# passive_balancing.net
KiCad netlist of a schematic drawn in Altium Designer
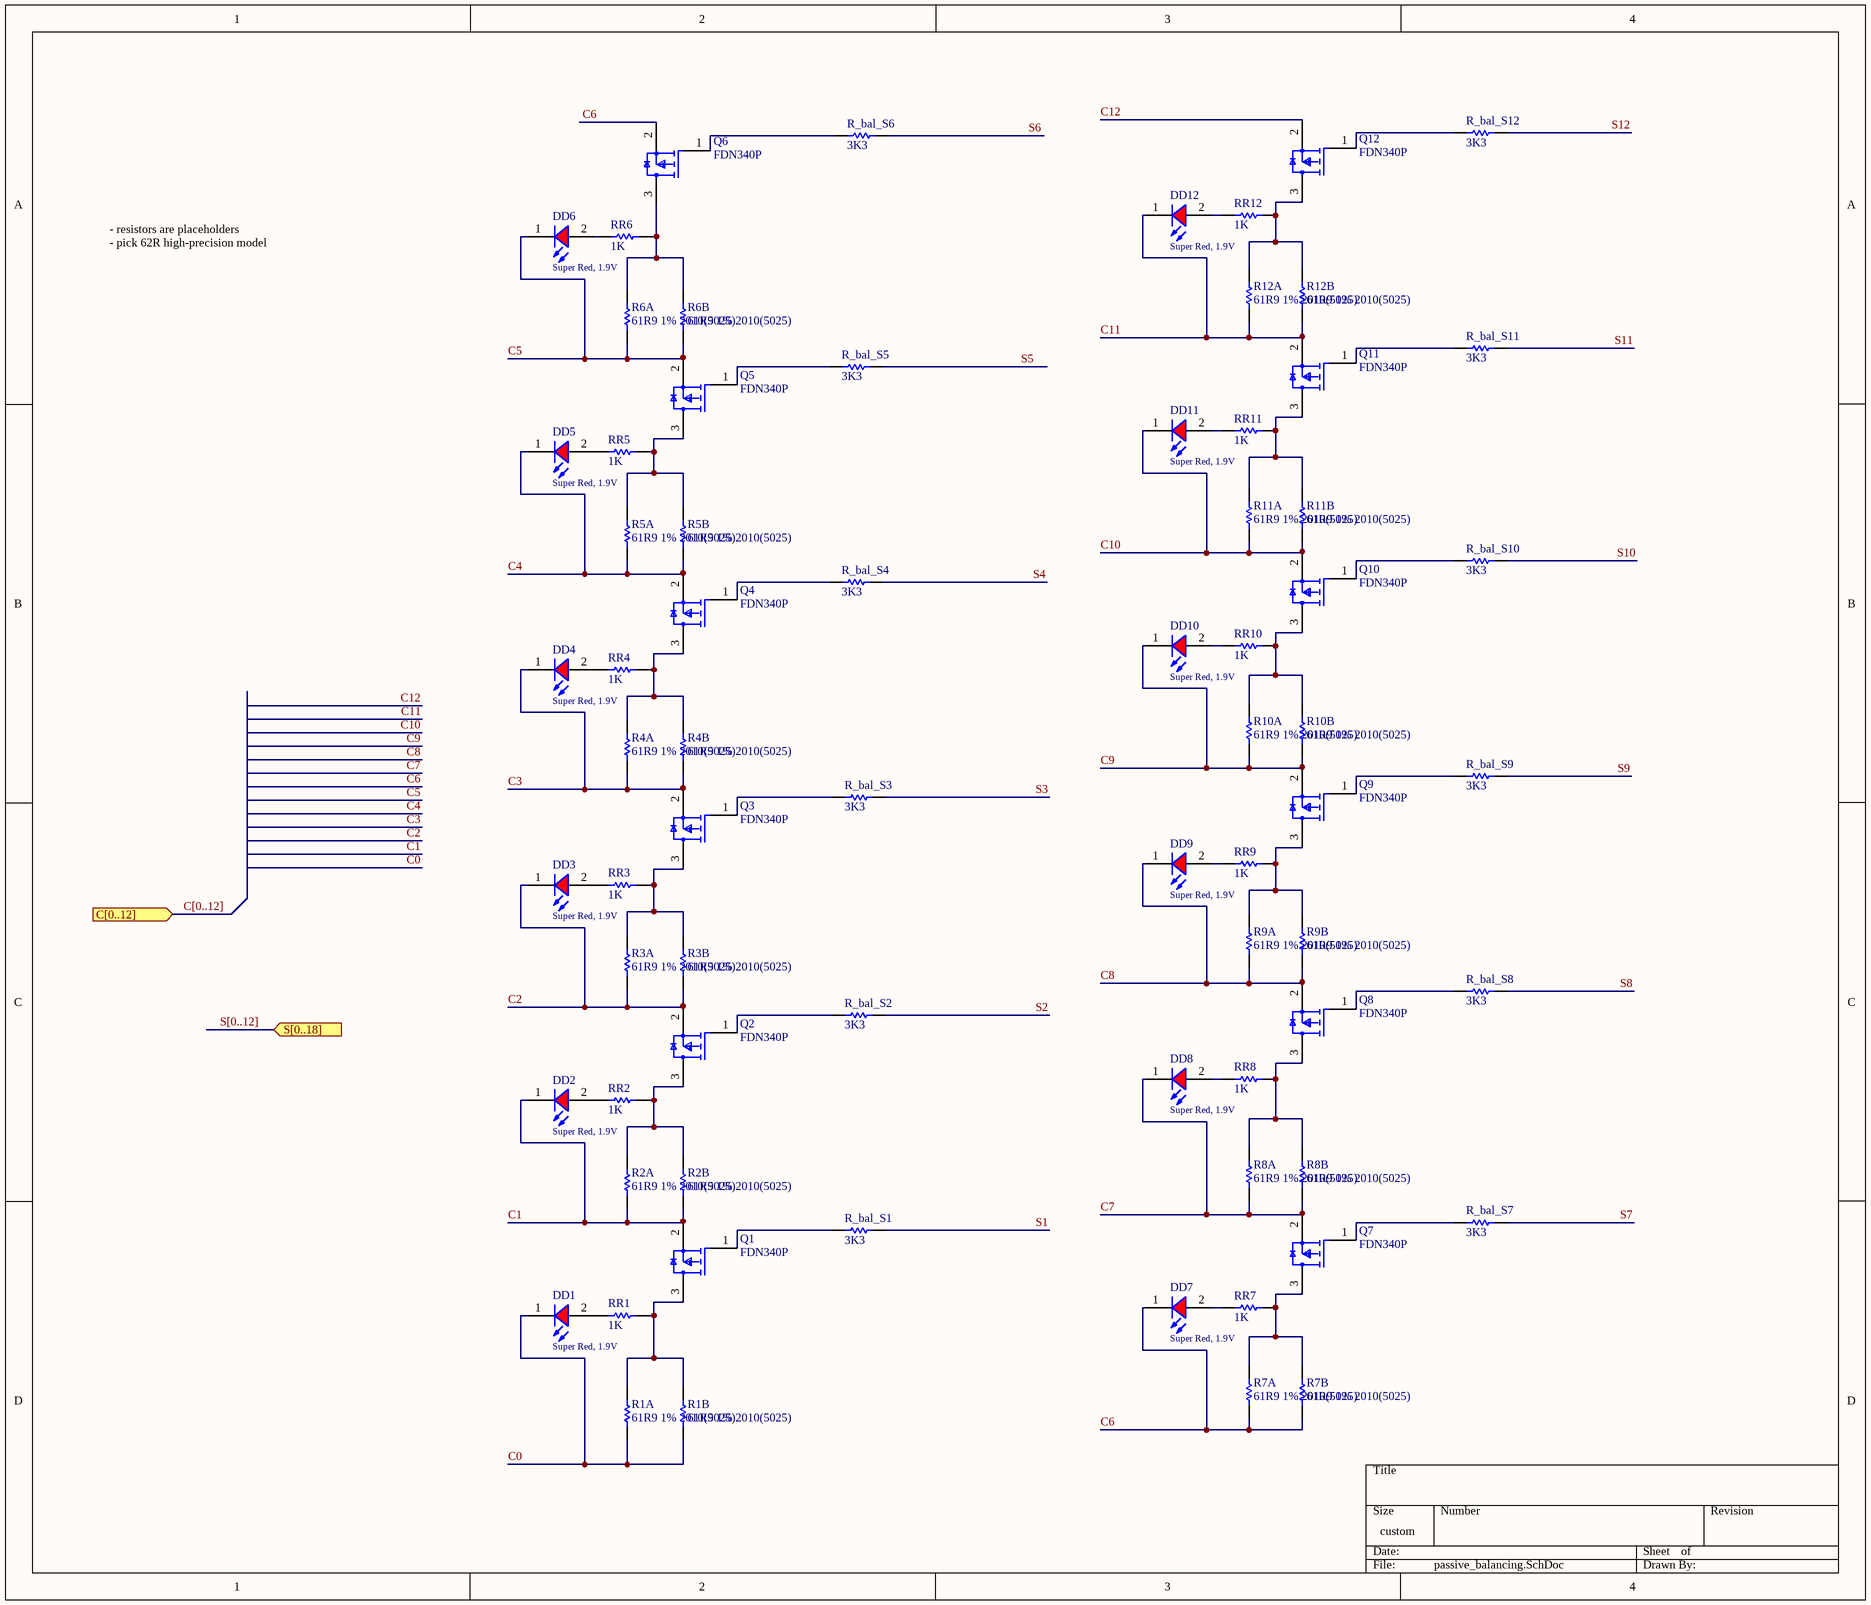
[diagram p0: passive_balancing.SchDoc]

(export (version "E")
  (design (tool "Eeschema 10.0.6"))
  (components
    (comp (ref "DD1")
      (value "Super Red, 1.9V")
      (footprint "WL-SMCW_0603_H=0.7mm")
      (description "WL-SMCW SMT Mono-color Chip LED Waterclear, size 0603, Super Red, 1.9V, 140deg")
      (fields (field (name "PART NUMBER") "150060SS75000") (field (name "PUBLISHER") "Wurth Elektronik"))
      (libsource (lib "LEDs") (part "150060SS75000"))
    )
    (comp (ref "DD2")
      (value "Super Red, 1.9V")
      (footprint "WL-SMCW_0603_H=0.7mm")
      (description "WL-SMCW SMT Mono-color Chip LED Waterclear, size 0603, Super Red, 1.9V, 140deg")
      (fields (field (name "PART NUMBER") "150060SS75000") (field (name "PUBLISHER") "Wurth Elektronik"))
      (libsource (lib "LEDs") (part "150060SS75000"))
    )
    (comp (ref "DD3")
      (value "Super Red, 1.9V")
      (footprint "WL-SMCW_0603_H=0.7mm")
      (description "WL-SMCW SMT Mono-color Chip LED Waterclear, size 0603, Super Red, 1.9V, 140deg")
      (fields (field (name "PART NUMBER") "150060SS75000") (field (name "PUBLISHER") "Wurth Elektronik"))
      (libsource (lib "LEDs") (part "150060SS75000"))
    )
    (comp (ref "DD4")
      (value "Super Red, 1.9V")
      (footprint "WL-SMCW_0603_H=0.7mm")
      (description "WL-SMCW SMT Mono-color Chip LED Waterclear, size 0603, Super Red, 1.9V, 140deg")
      (fields (field (name "PART NUMBER") "150060SS75000") (field (name "PUBLISHER") "Wurth Elektronik"))
      (libsource (lib "LEDs") (part "150060SS75000"))
    )
    (comp (ref "DD5")
      (value "Super Red, 1.9V")
      (footprint "WL-SMCW_0603_H=0.7mm")
      (description "WL-SMCW SMT Mono-color Chip LED Waterclear, size 0603, Super Red, 1.9V, 140deg")
      (fields (field (name "PART NUMBER") "150060SS75000") (field (name "PUBLISHER") "Wurth Elektronik"))
      (libsource (lib "LEDs") (part "150060SS75000"))
    )
    (comp (ref "DD6")
      (value "Super Red, 1.9V")
      (footprint "WL-SMCW_0603_H=0.7mm")
      (description "WL-SMCW SMT Mono-color Chip LED Waterclear, size 0603, Super Red, 1.9V, 140deg")
      (fields (field (name "PART NUMBER") "150060SS75000") (field (name "PUBLISHER") "Wurth Elektronik"))
      (libsource (lib "LEDs") (part "150060SS75000"))
    )
    (comp (ref "DD7")
      (value "Super Red, 1.9V")
      (footprint "WL-SMCW_0603_H=0.7mm")
      (description "WL-SMCW SMT Mono-color Chip LED Waterclear, size 0603, Super Red, 1.9V, 140deg")
      (fields (field (name "PART NUMBER") "150060SS75000") (field (name "PUBLISHER") "Wurth Elektronik"))
      (libsource (lib "LEDs") (part "150060SS75000"))
    )
    (comp (ref "DD8")
      (value "Super Red, 1.9V")
      (footprint "WL-SMCW_0603_H=0.7mm")
      (description "WL-SMCW SMT Mono-color Chip LED Waterclear, size 0603, Super Red, 1.9V, 140deg")
      (fields (field (name "PART NUMBER") "150060SS75000") (field (name "PUBLISHER") "Wurth Elektronik"))
      (libsource (lib "LEDs") (part "150060SS75000"))
    )
    (comp (ref "DD9")
      (value "Super Red, 1.9V")
      (footprint "WL-SMCW_0603_H=0.7mm")
      (description "WL-SMCW SMT Mono-color Chip LED Waterclear, size 0603, Super Red, 1.9V, 140deg")
      (fields (field (name "PART NUMBER") "150060SS75000") (field (name "PUBLISHER") "Wurth Elektronik"))
      (libsource (lib "LEDs") (part "150060SS75000"))
    )
    (comp (ref "DD10")
      (value "Super Red, 1.9V")
      (footprint "WL-SMCW_0603_H=0.7mm")
      (description "WL-SMCW SMT Mono-color Chip LED Waterclear, size 0603, Super Red, 1.9V, 140deg")
      (fields (field (name "PART NUMBER") "150060SS75000") (field (name "PUBLISHER") "Wurth Elektronik"))
      (libsource (lib "LEDs") (part "150060SS75000"))
    )
    (comp (ref "DD11")
      (value "Super Red, 1.9V")
      (footprint "WL-SMCW_0603_H=0.7mm")
      (description "WL-SMCW SMT Mono-color Chip LED Waterclear, size 0603, Super Red, 1.9V, 140deg")
      (fields (field (name "PART NUMBER") "150060SS75000") (field (name "PUBLISHER") "Wurth Elektronik"))
      (libsource (lib "LEDs") (part "150060SS75000"))
    )
    (comp (ref "DD12")
      (value "Super Red, 1.9V")
      (footprint "WL-SMCW_0603_H=0.7mm")
      (description "WL-SMCW SMT Mono-color Chip LED Waterclear, size 0603, Super Red, 1.9V, 140deg")
      (fields (field (name "PART NUMBER") "150060SS75000") (field (name "PUBLISHER") "Wurth Elektronik"))
      (libsource (lib "LEDs") (part "150060SS75000"))
    )
    (comp (ref "Q1")
      (value "FDN340P")
      (footprint "FP-527AG-MFG")
      (description "MOSFET P-CH 20V 2A SSOT3")
      (libsource (lib "Altium Content Vault") (part "d23f43cc42f60b967b7caccf14518fd"))
    )
    (comp (ref "Q2")
      (value "FDN340P")
      (footprint "FP-527AG-MFG")
      (description "MOSFET P-CH 20V 2A SSOT3")
      (libsource (lib "Altium Content Vault") (part "d23f43cc42f60b967b7caccf14518fd"))
    )
    (comp (ref "Q3")
      (value "FDN340P")
      (footprint "FP-527AG-MFG")
      (description "MOSFET P-CH 20V 2A SSOT3")
      (libsource (lib "Altium Content Vault") (part "d23f43cc42f60b967b7caccf14518fd"))
    )
    (comp (ref "Q4")
      (value "FDN340P")
      (footprint "FP-527AG-MFG")
      (description "MOSFET P-CH 20V 2A SSOT3")
      (libsource (lib "Altium Content Vault") (part "d23f43cc42f60b967b7caccf14518fd"))
    )
    (comp (ref "Q5")
      (value "FDN340P")
      (footprint "FP-527AG-MFG")
      (description "MOSFET P-CH 20V 2A SSOT3")
      (libsource (lib "Altium Content Vault") (part "d23f43cc42f60b967b7caccf14518fd"))
    )
    (comp (ref "Q6")
      (value "FDN340P")
      (footprint "FP-527AG-MFG")
      (description "MOSFET P-CH 20V 2A SSOT3")
      (libsource (lib "Altium Content Vault") (part "d23f43cc42f60b967b7caccf14518fd"))
    )
    (comp (ref "Q7")
      (value "FDN340P")
      (footprint "FP-527AG-MFG")
      (description "MOSFET P-CH 20V 2A SSOT3")
      (libsource (lib "Altium Content Vault") (part "d23f43cc42f60b967b7caccf14518fd"))
    )
    (comp (ref "Q8")
      (value "FDN340P")
      (footprint "FP-527AG-MFG")
      (description "MOSFET P-CH 20V 2A SSOT3")
      (libsource (lib "Altium Content Vault") (part "d23f43cc42f60b967b7caccf14518fd"))
    )
    (comp (ref "Q9")
      (value "FDN340P")
      (footprint "FP-527AG-MFG")
      (description "MOSFET P-CH 20V 2A SSOT3")
      (libsource (lib "Altium Content Vault") (part "d23f43cc42f60b967b7caccf14518fd"))
    )
    (comp (ref "Q10")
      (value "FDN340P")
      (footprint "FP-527AG-MFG")
      (description "MOSFET P-CH 20V 2A SSOT3")
      (libsource (lib "Altium Content Vault") (part "d23f43cc42f60b967b7caccf14518fd"))
    )
    (comp (ref "Q11")
      (value "FDN340P")
      (footprint "FP-527AG-MFG")
      (description "MOSFET P-CH 20V 2A SSOT3")
      (libsource (lib "Altium Content Vault") (part "d23f43cc42f60b967b7caccf14518fd"))
    )
    (comp (ref "Q12")
      (value "FDN340P")
      (footprint "FP-527AG-MFG")
      (description "MOSFET P-CH 20V 2A SSOT3")
      (libsource (lib "Altium Content Vault") (part "d23f43cc42f60b967b7caccf14518fd"))
    )
    (comp (ref "R1A")
      (value "61R9 1% 2010(5025)")
      (footprint "RESC2010(5025)_M")
      (description "61R9 0.75W 1% 2010 (5025 Metric)  SMD")
      (fields (field (name "POWER") "0.75 W") (field (name "TOLERANCE") "1 %"))
      (libsource (lib "Altium Content Vault") (part "RES"))
    )
    (comp (ref "R1B")
      (value "61R9 1% 2010(5025)")
      (footprint "RESC2010(5025)_M")
      (description "61R9 0.75W 1% 2010 (5025 Metric)  SMD")
      (fields (field (name "POWER") "0.75 W") (field (name "TOLERANCE") "1 %"))
      (libsource (lib "Altium Content Vault") (part "RES"))
    )
    (comp (ref "R2A")
      (value "61R9 1% 2010(5025)")
      (footprint "RESC2010(5025)_M")
      (description "61R9 0.75W 1% 2010 (5025 Metric)  SMD")
      (fields (field (name "POWER") "0.75 W") (field (name "TOLERANCE") "1 %"))
      (libsource (lib "Altium Content Vault") (part "RES"))
    )
    (comp (ref "R2B")
      (value "61R9 1% 2010(5025)")
      (footprint "RESC2010(5025)_M")
      (description "61R9 0.75W 1% 2010 (5025 Metric)  SMD")
      (fields (field (name "POWER") "0.75 W") (field (name "TOLERANCE") "1 %"))
      (libsource (lib "Altium Content Vault") (part "RES"))
    )
    (comp (ref "R3A")
      (value "61R9 1% 2010(5025)")
      (footprint "RESC2010(5025)_M")
      (description "61R9 0.75W 1% 2010 (5025 Metric)  SMD")
      (fields (field (name "POWER") "0.75 W") (field (name "TOLERANCE") "1 %"))
      (libsource (lib "Altium Content Vault") (part "RES"))
    )
    (comp (ref "R3B")
      (value "61R9 1% 2010(5025)")
      (footprint "RESC2010(5025)_M")
      (description "61R9 0.75W 1% 2010 (5025 Metric)  SMD")
      (fields (field (name "POWER") "0.75 W") (field (name "TOLERANCE") "1 %"))
      (libsource (lib "Altium Content Vault") (part "RES"))
    )
    (comp (ref "R4A")
      (value "61R9 1% 2010(5025)")
      (footprint "RESC2010(5025)_M")
      (description "61R9 0.75W 1% 2010 (5025 Metric)  SMD")
      (fields (field (name "POWER") "0.75 W") (field (name "TOLERANCE") "1 %"))
      (libsource (lib "Altium Content Vault") (part "RES"))
    )
    (comp (ref "R4B")
      (value "61R9 1% 2010(5025)")
      (footprint "RESC2010(5025)_M")
      (description "61R9 0.75W 1% 2010 (5025 Metric)  SMD")
      (fields (field (name "POWER") "0.75 W") (field (name "TOLERANCE") "1 %"))
      (libsource (lib "Altium Content Vault") (part "RES"))
    )
    (comp (ref "R5A")
      (value "61R9 1% 2010(5025)")
      (footprint "RESC2010(5025)_M")
      (description "61R9 0.75W 1% 2010 (5025 Metric)  SMD")
      (fields (field (name "POWER") "0.75 W") (field (name "TOLERANCE") "1 %"))
      (libsource (lib "Altium Content Vault") (part "RES"))
    )
    (comp (ref "R5B")
      (value "61R9 1% 2010(5025)")
      (footprint "RESC2010(5025)_M")
      (description "61R9 0.75W 1% 2010 (5025 Metric)  SMD")
      (fields (field (name "POWER") "0.75 W") (field (name "TOLERANCE") "1 %"))
      (libsource (lib "Altium Content Vault") (part "RES"))
    )
    (comp (ref "R6A")
      (value "61R9 1% 2010(5025)")
      (footprint "RESC2010(5025)_M")
      (description "61R9 0.75W 1% 2010 (5025 Metric)  SMD")
      (fields (field (name "POWER") "0.75 W") (field (name "TOLERANCE") "1 %"))
      (libsource (lib "Altium Content Vault") (part "RES"))
    )
    (comp (ref "R6B")
      (value "61R9 1% 2010(5025)")
      (footprint "RESC2010(5025)_M")
      (description "61R9 0.75W 1% 2010 (5025 Metric)  SMD")
      (fields (field (name "POWER") "0.75 W") (field (name "TOLERANCE") "1 %"))
      (libsource (lib "Altium Content Vault") (part "RES"))
    )
    (comp (ref "R7A")
      (value "61R9 1% 2010(5025)")
      (footprint "RESC2010(5025)_M")
      (description "61R9 0.75W 1% 2010 (5025 Metric)  SMD")
      (fields (field (name "POWER") "0.75 W") (field (name "TOLERANCE") "1 %"))
      (libsource (lib "Altium Content Vault") (part "RES"))
    )
    (comp (ref "R7B")
      (value "61R9 1% 2010(5025)")
      (footprint "RESC2010(5025)_M")
      (description "61R9 0.75W 1% 2010 (5025 Metric)  SMD")
      (fields (field (name "POWER") "0.75 W") (field (name "TOLERANCE") "1 %"))
      (libsource (lib "Altium Content Vault") (part "RES"))
    )
    (comp (ref "R8A")
      (value "61R9 1% 2010(5025)")
      (footprint "RESC2010(5025)_M")
      (description "61R9 0.75W 1% 2010 (5025 Metric)  SMD")
      (fields (field (name "POWER") "0.75 W") (field (name "TOLERANCE") "1 %"))
      (libsource (lib "Altium Content Vault") (part "RES"))
    )
    (comp (ref "R8B")
      (value "61R9 1% 2010(5025)")
      (footprint "RESC2010(5025)_M")
      (description "61R9 0.75W 1% 2010 (5025 Metric)  SMD")
      (fields (field (name "POWER") "0.75 W") (field (name "TOLERANCE") "1 %"))
      (libsource (lib "Altium Content Vault") (part "RES"))
    )
    (comp (ref "R9A")
      (value "61R9 1% 2010(5025)")
      (footprint "RESC2010(5025)_M")
      (description "61R9 0.75W 1% 2010 (5025 Metric)  SMD")
      (fields (field (name "POWER") "0.75 W") (field (name "TOLERANCE") "1 %"))
      (libsource (lib "Altium Content Vault") (part "RES"))
    )
    (comp (ref "R9B")
      (value "61R9 1% 2010(5025)")
      (footprint "RESC2010(5025)_M")
      (description "61R9 0.75W 1% 2010 (5025 Metric)  SMD")
      (fields (field (name "POWER") "0.75 W") (field (name "TOLERANCE") "1 %"))
      (libsource (lib "Altium Content Vault") (part "RES"))
    )
    (comp (ref "R10A")
      (value "61R9 1% 2010(5025)")
      (footprint "RESC2010(5025)_M")
      (description "61R9 0.75W 1% 2010 (5025 Metric)  SMD")
      (fields (field (name "POWER") "0.75 W") (field (name "TOLERANCE") "1 %"))
      (libsource (lib "Altium Content Vault") (part "RES"))
    )
    (comp (ref "R10B")
      (value "61R9 1% 2010(5025)")
      (footprint "RESC2010(5025)_M")
      (description "61R9 0.75W 1% 2010 (5025 Metric)  SMD")
      (fields (field (name "POWER") "0.75 W") (field (name "TOLERANCE") "1 %"))
      (libsource (lib "Altium Content Vault") (part "RES"))
    )
    (comp (ref "R11A")
      (value "61R9 1% 2010(5025)")
      (footprint "RESC2010(5025)_M")
      (description "61R9 0.75W 1% 2010 (5025 Metric)  SMD")
      (fields (field (name "POWER") "0.75 W") (field (name "TOLERANCE") "1 %"))
      (libsource (lib "Altium Content Vault") (part "RES"))
    )
    (comp (ref "R11B")
      (value "61R9 1% 2010(5025)")
      (footprint "RESC2010(5025)_M")
      (description "61R9 0.75W 1% 2010 (5025 Metric)  SMD")
      (fields (field (name "POWER") "0.75 W") (field (name "TOLERANCE") "1 %"))
      (libsource (lib "Altium Content Vault") (part "RES"))
    )
    (comp (ref "R12A")
      (value "61R9 1% 2010(5025)")
      (footprint "RESC2010(5025)_M")
      (description "61R9 0.75W 1% 2010 (5025 Metric)  SMD")
      (fields (field (name "POWER") "0.75 W") (field (name "TOLERANCE") "1 %"))
      (libsource (lib "Altium Content Vault") (part "RES"))
    )
    (comp (ref "R12B")
      (value "61R9 1% 2010(5025)")
      (footprint "RESC2010(5025)_M")
      (description "61R9 0.75W 1% 2010 (5025 Metric)  SMD")
      (fields (field (name "POWER") "0.75 W") (field (name "TOLERANCE") "1 %"))
      (libsource (lib "Altium Content Vault") (part "RES"))
    )
    (comp (ref "RR1")
      (value "1K")
      (footprint "RESC0603(1608)_N")
      (description "Chipwiderstand, SMD, Baureihe MC, 1%")
      (fields (field (name "MANUFACTURER") "Multicomp") (field (name "POWER") "100mW"))
      (libsource (lib "Res&Caps") (part "Res 1K"))
    )
    (comp (ref "RR2")
      (value "1K")
      (footprint "RESC0603(1608)_N")
      (description "Chipwiderstand, SMD, Baureihe MC, 1%")
      (fields (field (name "MANUFACTURER") "Multicomp") (field (name "POWER") "100mW"))
      (libsource (lib "Res&Caps") (part "Res 1K"))
    )
    (comp (ref "RR3")
      (value "1K")
      (footprint "RESC0603(1608)_N")
      (description "Chipwiderstand, SMD, Baureihe MC, 1%")
      (fields (field (name "MANUFACTURER") "Multicomp") (field (name "POWER") "100mW"))
      (libsource (lib "Res&Caps") (part "Res 1K"))
    )
    (comp (ref "RR4")
      (value "1K")
      (footprint "RESC0603(1608)_N")
      (description "Chipwiderstand, SMD, Baureihe MC, 1%")
      (fields (field (name "MANUFACTURER") "Multicomp") (field (name "POWER") "100mW"))
      (libsource (lib "Res&Caps") (part "Res 1K"))
    )
    (comp (ref "RR5")
      (value "1K")
      (footprint "RESC0603(1608)_N")
      (description "Chipwiderstand, SMD, Baureihe MC, 1%")
      (fields (field (name "MANUFACTURER") "Multicomp") (field (name "POWER") "100mW"))
      (libsource (lib "Res&Caps") (part "Res 1K"))
    )
    (comp (ref "RR6")
      (value "1K")
      (footprint "RESC0603(1608)_N")
      (description "Chipwiderstand, SMD, Baureihe MC, 1%")
      (fields (field (name "MANUFACTURER") "Multicomp") (field (name "POWER") "100mW"))
      (libsource (lib "Res&Caps") (part "Res 1K"))
    )
    (comp (ref "RR7")
      (value "1K")
      (footprint "RESC0603(1608)_N")
      (description "Chipwiderstand, SMD, Baureihe MC, 1%")
      (fields (field (name "MANUFACTURER") "Multicomp") (field (name "POWER") "100mW"))
      (libsource (lib "Res&Caps") (part "Res 1K"))
    )
    (comp (ref "RR8")
      (value "1K")
      (footprint "RESC0603(1608)_N")
      (description "Chipwiderstand, SMD, Baureihe MC, 1%")
      (fields (field (name "MANUFACTURER") "Multicomp") (field (name "POWER") "100mW"))
      (libsource (lib "Res&Caps") (part "Res 1K"))
    )
    (comp (ref "RR9")
      (value "1K")
      (footprint "RESC0603(1608)_N")
      (description "Chipwiderstand, SMD, Baureihe MC, 1%")
      (fields (field (name "MANUFACTURER") "Multicomp") (field (name "POWER") "100mW"))
      (libsource (lib "Res&Caps") (part "Res 1K"))
    )
    (comp (ref "RR10")
      (value "1K")
      (footprint "RESC0603(1608)_N")
      (description "Chipwiderstand, SMD, Baureihe MC, 1%")
      (fields (field (name "MANUFACTURER") "Multicomp") (field (name "POWER") "100mW"))
      (libsource (lib "Res&Caps") (part "Res 1K"))
    )
    (comp (ref "RR11")
      (value "1K")
      (footprint "RESC0603(1608)_N")
      (description "Chipwiderstand, SMD, Baureihe MC, 1%")
      (fields (field (name "MANUFACTURER") "Multicomp") (field (name "POWER") "100mW"))
      (libsource (lib "Res&Caps") (part "Res 1K"))
    )
    (comp (ref "RR12")
      (value "1K")
      (footprint "RESC0603(1608)_N")
      (description "Chipwiderstand, SMD, Baureihe MC, 1%")
      (fields (field (name "MANUFACTURER") "Multicomp") (field (name "POWER") "100mW"))
      (libsource (lib "Res&Caps") (part "Res 1K"))
    )
    (comp (ref "R_bal_S1")
      (value "3K3")
      (footprint "RESC0603(1608)_N")
      (description "Chipwiderstand, SMD, Baureihe MC, 1%")
      (fields (field (name "MANUFACTURER") "Multicomp") (field (name "POWER") "100mW"))
      (libsource (lib "Res&Caps") (part "Res 3K3"))
    )
    (comp (ref "R_bal_S2")
      (value "3K3")
      (footprint "RESC0603(1608)_N")
      (description "Chipwiderstand, SMD, Baureihe MC, 1%")
      (fields (field (name "MANUFACTURER") "Multicomp") (field (name "POWER") "100mW"))
      (libsource (lib "Res&Caps") (part "Res 3K3"))
    )
    (comp (ref "R_bal_S3")
      (value "3K3")
      (footprint "RESC0603(1608)_N")
      (description "Chipwiderstand, SMD, Baureihe MC, 1%")
      (fields (field (name "MANUFACTURER") "Multicomp") (field (name "POWER") "100mW"))
      (libsource (lib "Res&Caps") (part "Res 3K3"))
    )
    (comp (ref "R_bal_S4")
      (value "3K3")
      (footprint "RESC0603(1608)_N")
      (description "Chipwiderstand, SMD, Baureihe MC, 1%")
      (fields (field (name "MANUFACTURER") "Multicomp") (field (name "POWER") "100mW"))
      (libsource (lib "Res&Caps") (part "Res 3K3"))
    )
    (comp (ref "R_bal_S5")
      (value "3K3")
      (footprint "RESC0603(1608)_N")
      (description "Chipwiderstand, SMD, Baureihe MC, 1%")
      (fields (field (name "MANUFACTURER") "Multicomp") (field (name "POWER") "100mW"))
      (libsource (lib "Res&Caps") (part "Res 3K3"))
    )
    (comp (ref "R_bal_S6")
      (value "3K3")
      (footprint "RESC0603(1608)_N")
      (description "Chipwiderstand, SMD, Baureihe MC, 1%")
      (fields (field (name "MANUFACTURER") "Multicomp") (field (name "POWER") "100mW"))
      (libsource (lib "Res&Caps") (part "Res 3K3"))
    )
    (comp (ref "R_bal_S7")
      (value "3K3")
      (footprint "RESC0603(1608)_N")
      (description "Chipwiderstand, SMD, Baureihe MC, 1%")
      (fields (field (name "MANUFACTURER") "Multicomp") (field (name "POWER") "100mW"))
      (libsource (lib "Res&Caps") (part "Res 3K3"))
    )
    (comp (ref "R_bal_S8")
      (value "3K3")
      (footprint "RESC0603(1608)_N")
      (description "Chipwiderstand, SMD, Baureihe MC, 1%")
      (fields (field (name "MANUFACTURER") "Multicomp") (field (name "POWER") "100mW"))
      (libsource (lib "Res&Caps") (part "Res 3K3"))
    )
    (comp (ref "R_bal_S9")
      (value "3K3")
      (footprint "RESC0603(1608)_N")
      (description "Chipwiderstand, SMD, Baureihe MC, 1%")
      (fields (field (name "MANUFACTURER") "Multicomp") (field (name "POWER") "100mW"))
      (libsource (lib "Res&Caps") (part "Res 3K3"))
    )
    (comp (ref "R_bal_S10")
      (value "3K3")
      (footprint "RESC0603(1608)_N")
      (description "Chipwiderstand, SMD, Baureihe MC, 1%")
      (fields (field (name "MANUFACTURER") "Multicomp") (field (name "POWER") "100mW"))
      (libsource (lib "Res&Caps") (part "Res 3K3"))
    )
    (comp (ref "R_bal_S11")
      (value "3K3")
      (footprint "RESC0603(1608)_N")
      (description "Chipwiderstand, SMD, Baureihe MC, 1%")
      (fields (field (name "MANUFACTURER") "Multicomp") (field (name "POWER") "100mW"))
      (libsource (lib "Res&Caps") (part "Res 3K3"))
    )
    (comp (ref "R_bal_S12")
      (value "3K3")
      (footprint "RESC0603(1608)_N")
      (description "Chipwiderstand, SMD, Baureihe MC, 1%")
      (fields (field (name "MANUFACTURER") "Multicomp") (field (name "POWER") "100mW"))
      (libsource (lib "Res&Caps") (part "Res 3K3"))
    )
  )
  (nets
    (net (code "2") (name "/C0") (class "Default")
      (node (ref "DD1") (pin "1") (pinfunction "K_1") (pintype "passive"))
      (node (ref "R1A") (pin "1") (pinfunction "1_1") (pintype "passive"))
      (node (ref "R1B") (pin "1") (pinfunction "1_1") (pintype "passive"))
    )
    (net (code "3") (name "/C1") (class "Default")
      (node (ref "DD2") (pin "1") (pinfunction "K_1") (pintype "passive"))
      (node (ref "Q1") (pin "2") (pinfunction "S_2") (pintype "passive"))
      (node (ref "R2A") (pin "1") (pinfunction "1_1") (pintype "passive"))
      (node (ref "R2B") (pin "1") (pinfunction "1_1") (pintype "passive"))
    )
    (net (code "4") (name "/C2") (class "Default")
      (node (ref "DD3") (pin "1") (pinfunction "K_1") (pintype "passive"))
      (node (ref "Q2") (pin "2") (pinfunction "S_2") (pintype "passive"))
      (node (ref "R3A") (pin "1") (pinfunction "1_1") (pintype "passive"))
      (node (ref "R3B") (pin "1") (pinfunction "1_1") (pintype "passive"))
    )
    (net (code "5") (name "/C3") (class "Default")
      (node (ref "DD4") (pin "1") (pinfunction "K_1") (pintype "passive"))
      (node (ref "Q3") (pin "2") (pinfunction "S_2") (pintype "passive"))
      (node (ref "R4A") (pin "1") (pinfunction "1_1") (pintype "passive"))
      (node (ref "R4B") (pin "1") (pinfunction "1_1") (pintype "passive"))
    )
    (net (code "6") (name "/C4") (class "Default")
      (node (ref "DD5") (pin "1") (pinfunction "K_1") (pintype "passive"))
      (node (ref "Q4") (pin "2") (pinfunction "S_2") (pintype "passive"))
      (node (ref "R5A") (pin "1") (pinfunction "1_1") (pintype "passive"))
      (node (ref "R5B") (pin "1") (pinfunction "1_1") (pintype "passive"))
    )
    (net (code "7") (name "/C5") (class "Default")
      (node (ref "DD6") (pin "1") (pinfunction "K_1") (pintype "passive"))
      (node (ref "Q5") (pin "2") (pinfunction "S_2") (pintype "passive"))
      (node (ref "R6A") (pin "1") (pinfunction "1_1") (pintype "passive"))
      (node (ref "R6B") (pin "1") (pinfunction "1_1") (pintype "passive"))
    )
    (net (code "8") (name "/C6") (class "Default")
      (node (ref "DD7") (pin "1") (pinfunction "K_1") (pintype "passive"))
      (node (ref "Q6") (pin "2") (pinfunction "S_2") (pintype "passive"))
      (node (ref "R7A") (pin "1") (pinfunction "1_1") (pintype "passive"))
      (node (ref "R7B") (pin "1") (pinfunction "1_1") (pintype "passive"))
    )
    (net (code "9") (name "/C7") (class "Default")
      (node (ref "DD8") (pin "1") (pinfunction "K_1") (pintype "passive"))
      (node (ref "Q7") (pin "2") (pinfunction "S_2") (pintype "passive"))
      (node (ref "R8A") (pin "1") (pinfunction "1_1") (pintype "passive"))
      (node (ref "R8B") (pin "1") (pinfunction "1_1") (pintype "passive"))
    )
    (net (code "10") (name "/C8") (class "Default")
      (node (ref "DD9") (pin "1") (pinfunction "K_1") (pintype "passive"))
      (node (ref "Q8") (pin "2") (pinfunction "S_2") (pintype "passive"))
      (node (ref "R9A") (pin "1") (pinfunction "1_1") (pintype "passive"))
      (node (ref "R9B") (pin "1") (pinfunction "1_1") (pintype "passive"))
    )
    (net (code "11") (name "/C9") (class "Default")
      (node (ref "DD10") (pin "1") (pinfunction "K_1") (pintype "passive"))
      (node (ref "Q9") (pin "2") (pinfunction "S_2") (pintype "passive"))
      (node (ref "R10A") (pin "1") (pinfunction "1_1") (pintype "passive"))
      (node (ref "R10B") (pin "1") (pinfunction "1_1") (pintype "passive"))
    )
    (net (code "12") (name "/C10") (class "Default")
      (node (ref "DD11") (pin "1") (pinfunction "K_1") (pintype "passive"))
      (node (ref "Q10") (pin "2") (pinfunction "S_2") (pintype "passive"))
      (node (ref "R11A") (pin "1") (pinfunction "1_1") (pintype "passive"))
      (node (ref "R11B") (pin "1") (pinfunction "1_1") (pintype "passive"))
    )
    (net (code "13") (name "/C11") (class "Default")
      (node (ref "DD12") (pin "1") (pinfunction "K_1") (pintype "passive"))
      (node (ref "Q11") (pin "2") (pinfunction "S_2") (pintype "passive"))
      (node (ref "R12A") (pin "1") (pinfunction "1_1") (pintype "passive"))
      (node (ref "R12B") (pin "1") (pinfunction "1_1") (pintype "passive"))
    )
    (net (code "14") (name "/C12") (class "Default")
      (node (ref "Q12") (pin "2") (pinfunction "S_2") (pintype "passive"))
    )
    (net (code "16") (name "/S1") (class "Default")
      (node (ref "R_bal_S1") (pin "2") (pinfunction "2_2") (pintype "passive"))
    )
    (net (code "17") (name "/S2") (class "Default")
      (node (ref "R_bal_S2") (pin "2") (pinfunction "2_2") (pintype "passive"))
    )
    (net (code "18") (name "/S3") (class "Default")
      (node (ref "R_bal_S3") (pin "2") (pinfunction "2_2") (pintype "passive"))
    )
    (net (code "19") (name "/S4") (class "Default")
      (node (ref "R_bal_S4") (pin "2") (pinfunction "2_2") (pintype "passive"))
    )
    (net (code "20") (name "/S5") (class "Default")
      (node (ref "R_bal_S5") (pin "2") (pinfunction "2_2") (pintype "passive"))
    )
    (net (code "21") (name "/S6") (class "Default")
      (node (ref "R_bal_S6") (pin "2") (pinfunction "2_2") (pintype "passive"))
    )
    (net (code "22") (name "/S7") (class "Default")
      (node (ref "R_bal_S7") (pin "2") (pinfunction "2_2") (pintype "passive"))
    )
    (net (code "23") (name "/S8") (class "Default")
      (node (ref "R_bal_S8") (pin "2") (pinfunction "2_2") (pintype "passive"))
    )
    (net (code "24") (name "/S9") (class "Default")
      (node (ref "R_bal_S9") (pin "2") (pinfunction "2_2") (pintype "passive"))
    )
    (net (code "25") (name "/S10") (class "Default")
      (node (ref "R_bal_S10") (pin "2") (pinfunction "2_2") (pintype "passive"))
    )
    (net (code "26") (name "/S11") (class "Default")
      (node (ref "R_bal_S11") (pin "2") (pinfunction "2_2") (pintype "passive"))
    )
    (net (code "27") (name "/S12") (class "Default")
      (node (ref "R_bal_S12") (pin "2") (pinfunction "2_2") (pintype "passive"))
    )
    (net (code "29") (name "Net-(DD1-A)") (class "Default")
      (node (ref "DD1") (pin "2") (pinfunction "A_2") (pintype "passive"))
      (node (ref "RR1") (pin "2") (pinfunction "2_2") (pintype "passive"))
    )
    (net (code "30") (name "Net-(DD2-A)") (class "Default")
      (node (ref "DD2") (pin "2") (pinfunction "A_2") (pintype "passive"))
      (node (ref "RR2") (pin "2") (pinfunction "2_2") (pintype "passive"))
    )
    (net (code "31") (name "Net-(DD3-A)") (class "Default")
      (node (ref "DD3") (pin "2") (pinfunction "A_2") (pintype "passive"))
      (node (ref "RR3") (pin "2") (pinfunction "2_2") (pintype "passive"))
    )
    (net (code "32") (name "Net-(DD4-A)") (class "Default")
      (node (ref "DD4") (pin "2") (pinfunction "A_2") (pintype "passive"))
      (node (ref "RR4") (pin "2") (pinfunction "2_2") (pintype "passive"))
    )
    (net (code "33") (name "Net-(DD5-A)") (class "Default")
      (node (ref "DD5") (pin "2") (pinfunction "A_2") (pintype "passive"))
      (node (ref "RR5") (pin "2") (pinfunction "2_2") (pintype "passive"))
    )
    (net (code "34") (name "Net-(DD6-A)") (class "Default")
      (node (ref "DD6") (pin "2") (pinfunction "A_2") (pintype "passive"))
      (node (ref "RR6") (pin "2") (pinfunction "2_2") (pintype "passive"))
    )
    (net (code "35") (name "Net-(DD7-A)") (class "Default")
      (node (ref "DD7") (pin "2") (pinfunction "A_2") (pintype "passive"))
      (node (ref "RR7") (pin "2") (pinfunction "2_2") (pintype "passive"))
    )
    (net (code "36") (name "Net-(DD8-A)") (class "Default")
      (node (ref "DD8") (pin "2") (pinfunction "A_2") (pintype "passive"))
      (node (ref "RR8") (pin "2") (pinfunction "2_2") (pintype "passive"))
    )
    (net (code "37") (name "Net-(DD9-A)") (class "Default")
      (node (ref "DD9") (pin "2") (pinfunction "A_2") (pintype "passive"))
      (node (ref "RR9") (pin "2") (pinfunction "2_2") (pintype "passive"))
    )
    (net (code "38") (name "Net-(DD10-A)") (class "Default")
      (node (ref "DD10") (pin "2") (pinfunction "A_2") (pintype "passive"))
      (node (ref "RR10") (pin "2") (pinfunction "2_2") (pintype "passive"))
    )
    (net (code "39") (name "Net-(DD11-A)") (class "Default")
      (node (ref "DD11") (pin "2") (pinfunction "A_2") (pintype "passive"))
      (node (ref "RR11") (pin "2") (pinfunction "2_2") (pintype "passive"))
    )
    (net (code "40") (name "Net-(DD12-A)") (class "Default")
      (node (ref "DD12") (pin "2") (pinfunction "A_2") (pintype "passive"))
      (node (ref "RR12") (pin "2") (pinfunction "2_2") (pintype "passive"))
    )
    (net (code "41") (name "Net-(Q1-D)") (class "Default")
      (node (ref "Q1") (pin "3") (pinfunction "D_3") (pintype "passive"))
      (node (ref "R1A") (pin "2") (pinfunction "2_2") (pintype "passive"))
      (node (ref "R1B") (pin "2") (pinfunction "2_2") (pintype "passive"))
      (node (ref "RR1") (pin "1") (pinfunction "1_1") (pintype "passive"))
    )
    (net (code "42") (name "Net-(Q1-G)") (class "Default")
      (node (ref "Q1") (pin "1") (pinfunction "G_1") (pintype "passive"))
      (node (ref "R_bal_S1") (pin "1") (pinfunction "1_1") (pintype "passive"))
    )
    (net (code "43") (name "Net-(Q2-D)") (class "Default")
      (node (ref "Q2") (pin "3") (pinfunction "D_3") (pintype "passive"))
      (node (ref "R2A") (pin "2") (pinfunction "2_2") (pintype "passive"))
      (node (ref "R2B") (pin "2") (pinfunction "2_2") (pintype "passive"))
      (node (ref "RR2") (pin "1") (pinfunction "1_1") (pintype "passive"))
    )
    (net (code "44") (name "Net-(Q2-G)") (class "Default")
      (node (ref "Q2") (pin "1") (pinfunction "G_1") (pintype "passive"))
      (node (ref "R_bal_S2") (pin "1") (pinfunction "1_1") (pintype "passive"))
    )
    (net (code "45") (name "Net-(Q3-D)") (class "Default")
      (node (ref "Q3") (pin "3") (pinfunction "D_3") (pintype "passive"))
      (node (ref "R3A") (pin "2") (pinfunction "2_2") (pintype "passive"))
      (node (ref "R3B") (pin "2") (pinfunction "2_2") (pintype "passive"))
      (node (ref "RR3") (pin "1") (pinfunction "1_1") (pintype "passive"))
    )
    (net (code "46") (name "Net-(Q3-G)") (class "Default")
      (node (ref "Q3") (pin "1") (pinfunction "G_1") (pintype "passive"))
      (node (ref "R_bal_S3") (pin "1") (pinfunction "1_1") (pintype "passive"))
    )
    (net (code "47") (name "Net-(Q4-D)") (class "Default")
      (node (ref "Q4") (pin "3") (pinfunction "D_3") (pintype "passive"))
      (node (ref "R4A") (pin "2") (pinfunction "2_2") (pintype "passive"))
      (node (ref "R4B") (pin "2") (pinfunction "2_2") (pintype "passive"))
      (node (ref "RR4") (pin "1") (pinfunction "1_1") (pintype "passive"))
    )
    (net (code "48") (name "Net-(Q4-G)") (class "Default")
      (node (ref "Q4") (pin "1") (pinfunction "G_1") (pintype "passive"))
      (node (ref "R_bal_S4") (pin "1") (pinfunction "1_1") (pintype "passive"))
    )
    (net (code "49") (name "Net-(Q5-D)") (class "Default")
      (node (ref "Q5") (pin "3") (pinfunction "D_3") (pintype "passive"))
      (node (ref "R5A") (pin "2") (pinfunction "2_2") (pintype "passive"))
      (node (ref "R5B") (pin "2") (pinfunction "2_2") (pintype "passive"))
      (node (ref "RR5") (pin "1") (pinfunction "1_1") (pintype "passive"))
    )
    (net (code "50") (name "Net-(Q5-G)") (class "Default")
      (node (ref "Q5") (pin "1") (pinfunction "G_1") (pintype "passive"))
      (node (ref "R_bal_S5") (pin "1") (pinfunction "1_1") (pintype "passive"))
    )
    (net (code "51") (name "Net-(Q6-D)") (class "Default")
      (node (ref "Q6") (pin "3") (pinfunction "D_3") (pintype "passive"))
      (node (ref "R6A") (pin "2") (pinfunction "2_2") (pintype "passive"))
      (node (ref "R6B") (pin "2") (pinfunction "2_2") (pintype "passive"))
      (node (ref "RR6") (pin "1") (pinfunction "1_1") (pintype "passive"))
    )
    (net (code "52") (name "Net-(Q6-G)") (class "Default")
      (node (ref "Q6") (pin "1") (pinfunction "G_1") (pintype "passive"))
      (node (ref "R_bal_S6") (pin "1") (pinfunction "1_1") (pintype "passive"))
    )
    (net (code "53") (name "Net-(Q7-D)") (class "Default")
      (node (ref "Q7") (pin "3") (pinfunction "D_3") (pintype "passive"))
      (node (ref "R7A") (pin "2") (pinfunction "2_2") (pintype "passive"))
      (node (ref "R7B") (pin "2") (pinfunction "2_2") (pintype "passive"))
      (node (ref "RR7") (pin "1") (pinfunction "1_1") (pintype "passive"))
    )
    (net (code "54") (name "Net-(Q7-G)") (class "Default")
      (node (ref "Q7") (pin "1") (pinfunction "G_1") (pintype "passive"))
      (node (ref "R_bal_S7") (pin "1") (pinfunction "1_1") (pintype "passive"))
    )
    (net (code "55") (name "Net-(Q8-D)") (class "Default")
      (node (ref "Q8") (pin "3") (pinfunction "D_3") (pintype "passive"))
      (node (ref "R8A") (pin "2") (pinfunction "2_2") (pintype "passive"))
      (node (ref "R8B") (pin "2") (pinfunction "2_2") (pintype "passive"))
      (node (ref "RR8") (pin "1") (pinfunction "1_1") (pintype "passive"))
    )
    (net (code "56") (name "Net-(Q8-G)") (class "Default")
      (node (ref "Q8") (pin "1") (pinfunction "G_1") (pintype "passive"))
      (node (ref "R_bal_S8") (pin "1") (pinfunction "1_1") (pintype "passive"))
    )
    (net (code "57") (name "Net-(Q9-D)") (class "Default")
      (node (ref "Q9") (pin "3") (pinfunction "D_3") (pintype "passive"))
      (node (ref "R9A") (pin "2") (pinfunction "2_2") (pintype "passive"))
      (node (ref "R9B") (pin "2") (pinfunction "2_2") (pintype "passive"))
      (node (ref "RR9") (pin "1") (pinfunction "1_1") (pintype "passive"))
    )
    (net (code "58") (name "Net-(Q9-G)") (class "Default")
      (node (ref "Q9") (pin "1") (pinfunction "G_1") (pintype "passive"))
      (node (ref "R_bal_S9") (pin "1") (pinfunction "1_1") (pintype "passive"))
    )
    (net (code "59") (name "Net-(Q10-D)") (class "Default")
      (node (ref "Q10") (pin "3") (pinfunction "D_3") (pintype "passive"))
      (node (ref "R10A") (pin "2") (pinfunction "2_2") (pintype "passive"))
      (node (ref "R10B") (pin "2") (pinfunction "2_2") (pintype "passive"))
      (node (ref "RR10") (pin "1") (pinfunction "1_1") (pintype "passive"))
    )
    (net (code "60") (name "Net-(Q10-G)") (class "Default")
      (node (ref "Q10") (pin "1") (pinfunction "G_1") (pintype "passive"))
      (node (ref "R_bal_S10") (pin "1") (pinfunction "1_1") (pintype "passive"))
    )
    (net (code "61") (name "Net-(Q11-D)") (class "Default")
      (node (ref "Q11") (pin "3") (pinfunction "D_3") (pintype "passive"))
      (node (ref "R11A") (pin "2") (pinfunction "2_2") (pintype "passive"))
      (node (ref "R11B") (pin "2") (pinfunction "2_2") (pintype "passive"))
      (node (ref "RR11") (pin "1") (pinfunction "1_1") (pintype "passive"))
    )
    (net (code "62") (name "Net-(Q11-G)") (class "Default")
      (node (ref "Q11") (pin "1") (pinfunction "G_1") (pintype "passive"))
      (node (ref "R_bal_S11") (pin "1") (pinfunction "1_1") (pintype "passive"))
    )
    (net (code "63") (name "Net-(Q12-D)") (class "Default")
      (node (ref "Q12") (pin "3") (pinfunction "D_3") (pintype "passive"))
      (node (ref "R12A") (pin "2") (pinfunction "2_2") (pintype "passive"))
      (node (ref "R12B") (pin "2") (pinfunction "2_2") (pintype "passive"))
      (node (ref "RR12") (pin "1") (pinfunction "1_1") (pintype "passive"))
    )
    (net (code "64") (name "Net-(Q12-G)") (class "Default")
      (node (ref "Q12") (pin "1") (pinfunction "G_1") (pintype "passive"))
      (node (ref "R_bal_S12") (pin "1") (pinfunction "1_1") (pintype "passive"))
    )
  )
)
